# Board_OLED.net
KiCad netlist of a schematic drawn in EAGLE
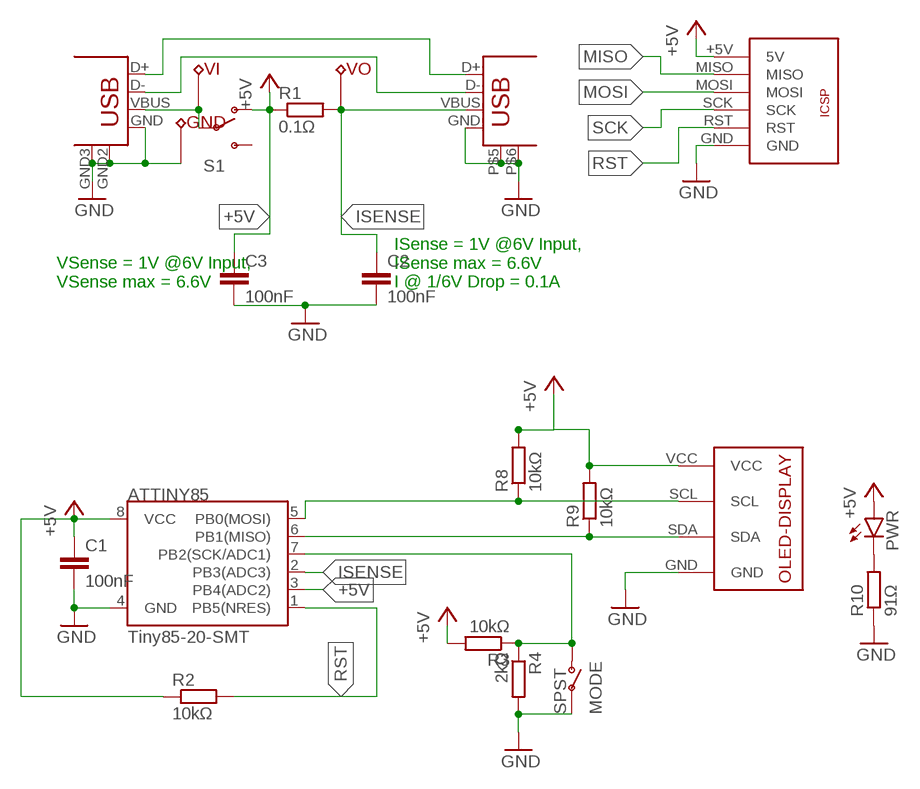
[diagram p0: schematic, sheet 1]

(export (version "E")
  (design (tool "Eeschema 10.0.6"))
  (components
    (comp (ref "ATTINY85")
      (value "Tiny85-20-SMT")
      (footprint "eagle-import:SO08-EIAJ")
      (libsource (lib "eagle-import") (part "ATTINY45TINY85-20-SMT"))
    )
    (comp (ref "C1")
      (value "100nF")
      (footprint "eagle-import:C0603")
      (libsource (lib "eagle-import") (part "C-EUC0603"))
    )
    (comp (ref "C2")
      (value "100nF")
      (footprint "eagle-import:C0603")
      (libsource (lib "eagle-import") (part "C-EUC0603"))
    )
    (comp (ref "C3")
      (value "100nF")
      (footprint "eagle-import:C0603")
      (libsource (lib "eagle-import") (part "C-EUC0603"))
    )
    (comp (ref "GND")
      (value "TESTPOINT0.5MM-DRILL-WIRE-LOOP")
      (footprint "eagle-import:TP-0.5MM-DUAL")
      (libsource (lib "eagle-import") (part "TESTPOINT0.5MM-DRILL-WIRE-LOOP"))
    )
    (comp (ref "INPUT")
      (value "USB+SHIELDTHROUGHHOLE-MALE")
      (footprint "eagle-import:USB-A-H")
      (libsource (lib "eagle-import") (part "USB+SHIELDTHROUGHHOLE-MALE"))
    )
    (comp (ref "MODE")
      (value "SPST")
      (footprint "eagle-import:WUERTH-SPST-SMD")
      (libsource (lib "eagle-import") (part "SPST"))
    )
    (comp (ref "OUTPUT")
      (value "USB+SHIELDTHROUGHOLE-FEMALE")
      (footprint "eagle-import:USB-A-S-SILK-THROUGHHOLE")
      (libsource (lib "eagle-import") (part "USB+SHIELDTHROUGHOLE-FEMALE"))
    )
    (comp (ref "PWR")
      (value "LED0603")
      (footprint "eagle-import:LED-0603")
      (libsource (lib "eagle-import") (part "LED0603"))
    )
    (comp (ref "R1")
      (value "0.1Ω")
      (footprint "eagle-import:R2512")
      (libsource (lib "eagle-import") (part "R-EU_R2512"))
    )
    (comp (ref "R2")
      (value "10kΩ")
      (footprint "eagle-import:R0603")
      (libsource (lib "eagle-import") (part "R-EU_R0603"))
    )
    (comp (ref "R3")
      (value "10kΩ")
      (footprint "eagle-import:R0603")
      (libsource (lib "eagle-import") (part "R-EU_R0603"))
    )
    (comp (ref "R4")
      (value "2kΩ")
      (footprint "eagle-import:R0603")
      (libsource (lib "eagle-import") (part "R-EU_R0603"))
    )
    (comp (ref "R8")
      (value "10kΩ")
      (footprint "eagle-import:R0603")
      (libsource (lib "eagle-import") (part "R-EU_R0603"))
    )
    (comp (ref "R9")
      (value "10kΩ")
      (footprint "eagle-import:R0603")
      (libsource (lib "eagle-import") (part "R-EU_R0603"))
    )
    (comp (ref "R10")
      (value "91Ω")
      (footprint "eagle-import:R0603")
      (libsource (lib "eagle-import") (part "R-EU_R0603"))
    )
    (comp (ref "S1")
      (value "SWITCH-SPDT-SMD-A")
      (footprint "eagle-import:SWITCH-SPST-SMD-A")
      (libsource (lib "eagle-import") (part "SWITCH-SPDT-SMD-A"))
    )
    (comp (ref "U$1")
      (value "ICSPSMD")
      (footprint "eagle-import:ICSP-SMD")
      (libsource (lib "eagle-import") (part "ICSPSMD"))
    )
    (comp (ref "U$2")
      (value "OLED-I2CGND-VCC-SCL-SDA")
      (footprint "eagle-import:OLED-I2C")
      (libsource (lib "eagle-import") (part "OLED-I2CGND-VCC-SCL-SDA"))
    )
    (comp (ref "VI")
      (value "TESTPOINT0.5MM-DRILL-WIRE-LOOP")
      (footprint "eagle-import:TP-0.5MM-DUAL")
      (libsource (lib "eagle-import") (part "TESTPOINT0.5MM-DRILL-WIRE-LOOP"))
    )
    (comp (ref "VO")
      (value "TESTPOINT0.5MM-DRILL-WIRE-LOOP")
      (footprint "eagle-import:TP-0.5MM-DUAL")
      (libsource (lib "eagle-import") (part "TESTPOINT0.5MM-DRILL-WIRE-LOOP"))
    )
  )
  (nets
    (net (code "1") (name "+5V") (class "Default")
      (node (ref "ATTINY85") (pin "3") (pinfunction "PB4(ADC2)_3") (pintype "bidirectional"))
      (node (ref "ATTINY85") (pin "8") (pinfunction "VCC_8") (pintype "bidirectional"))
      (node (ref "C1") (pin "1") (pinfunction "1_1") (pintype "passive"))
      (node (ref "C3") (pin "1") (pinfunction "1_1") (pintype "passive"))
      (node (ref "PWR") (pin "A") (pinfunction "A_A") (pintype "passive"))
      (node (ref "R1") (pin "1") (pinfunction "1_1") (pintype "passive"))
      (node (ref "R2") (pin "1") (pinfunction "1_1") (pintype "passive"))
      (node (ref "R3") (pin "2") (pinfunction "2_2") (pintype "passive"))
      (node (ref "R8") (pin "2") (pinfunction "2_2") (pintype "passive"))
      (node (ref "R9") (pin "2") (pinfunction "2_2") (pintype "passive"))
      (node (ref "S1") (pin "1") (pinfunction "O_1") (pintype "passive"))
      (node (ref "U$1") (pin "+5V") (pinfunction "5V_+5V") (pintype "bidirectional"))
      (node (ref "U$2") (pin "VCC") (pinfunction "VCC_VCC") (pintype "bidirectional"))
    )
    (net (code "2") (name "GND") (class "Default")
      (node (ref "ATTINY85") (pin "4") (pinfunction "GND_4") (pintype "bidirectional"))
      (node (ref "C1") (pin "2") (pinfunction "2_2") (pintype "passive"))
      (node (ref "C2") (pin "2") (pinfunction "2_2") (pintype "passive"))
      (node (ref "C3") (pin "2") (pinfunction "2_2") (pintype "passive"))
      (node (ref "GND") (pin "P$1") (pinfunction "TP_P$1") (pintype "bidirectional"))
      (node (ref "GND") (pin "P$2") (pinfunction "TP_P$2") (pintype "bidirectional"))
      (node (ref "INPUT") (pin "GND") (pinfunction "GND_GND") (pintype "bidirectional"))
      (node (ref "INPUT") (pin "GND2") (pinfunction "S1_GND2") (pintype "bidirectional"))
      (node (ref "INPUT") (pin "GND3") (pinfunction "S2_GND3") (pintype "bidirectional"))
      (node (ref "MODE") (pin "1") (pinfunction "P_1") (pintype "passive"))
      (node (ref "MODE") (pin "3") (pinfunction "P_3") (pintype "passive"))
      (node (ref "OUTPUT") (pin "GND") (pinfunction "GND_GND") (pintype "bidirectional"))
      (node (ref "OUTPUT") (pin "P$5") (pinfunction "S1_P$5") (pintype "bidirectional"))
      (node (ref "OUTPUT") (pin "P$6") (pinfunction "S2_P$6") (pintype "bidirectional"))
      (node (ref "R10") (pin "1") (pinfunction "1_1") (pintype "passive"))
      (node (ref "R4") (pin "2") (pinfunction "2_2") (pintype "passive"))
      (node (ref "U$1") (pin "GND") (pinfunction "GND_GND") (pintype "bidirectional"))
      (node (ref "U$2") (pin "GND") (pinfunction "GND_GND") (pintype "bidirectional"))
    )
    (net (code "3") (name "ISENSE") (class "Default")
      (node (ref "ATTINY85") (pin "2") (pinfunction "PB3(ADC3)_2") (pintype "bidirectional"))
      (node (ref "C2") (pin "1") (pinfunction "1_1") (pintype "passive"))
      (node (ref "OUTPUT") (pin "VBUS") (pinfunction "VBUS_VBUS") (pintype "bidirectional"))
      (node (ref "R1") (pin "2") (pinfunction "2_2") (pintype "passive"))
      (node (ref "VO") (pin "P$1") (pinfunction "TP_P$1") (pintype "bidirectional"))
      (node (ref "VO") (pin "P$2") (pinfunction "TP_P$2") (pintype "bidirectional"))
    )
    (net (code "4") (name "MISO") (class "Default")
      (node (ref "ATTINY85") (pin "6") (pinfunction "PB1(MISO)_6") (pintype "bidirectional"))
      (node (ref "R9") (pin "1") (pinfunction "1_1") (pintype "passive"))
      (node (ref "U$1") (pin "MISO") (pinfunction "MISO_MISO") (pintype "bidirectional"))
      (node (ref "U$2") (pin "SDA") (pinfunction "SDA_SDA") (pintype "bidirectional"))
    )
    (net (code "5") (name "MOSI") (class "Default")
      (node (ref "ATTINY85") (pin "5") (pinfunction "PB0(MOSI)_5") (pintype "bidirectional"))
      (node (ref "R8") (pin "1") (pinfunction "1_1") (pintype "passive"))
      (node (ref "U$1") (pin "MOSI") (pinfunction "MOSI_MOSI") (pintype "bidirectional"))
      (node (ref "U$2") (pin "SCL") (pinfunction "SCL_SCL") (pintype "bidirectional"))
    )
    (net (code "6") (name "Net-(INPUT-PadD+)") (class "Default")
      (node (ref "INPUT") (pin "D+") (pinfunction "D+_D+") (pintype "bidirectional"))
      (node (ref "OUTPUT") (pin "D+") (pinfunction "D+_D+") (pintype "bidirectional"))
    )
    (net (code "7") (name "Net-(INPUT-PadD-)") (class "Default")
      (node (ref "INPUT") (pin "D-") (pinfunction "D-_D-") (pintype "bidirectional"))
      (node (ref "OUTPUT") (pin "D-") (pinfunction "D-_D-") (pintype "bidirectional"))
    )
    (net (code "8") (name "Net-(PWR-PadC)") (class "Default")
      (node (ref "PWR") (pin "C") (pinfunction "C_C") (pintype "passive"))
      (node (ref "R10") (pin "2") (pinfunction "2_2") (pintype "passive"))
    )
    (net (code "9") (name "Net-(S1-P)") (class "Default")
      (node (ref "INPUT") (pin "VBUS") (pinfunction "VBUS_VBUS") (pintype "bidirectional"))
      (node (ref "S1") (pin "2") (pinfunction "P_2") (pintype "passive"))
      (node (ref "VI") (pin "P$1") (pinfunction "TP_P$1") (pintype "bidirectional"))
      (node (ref "VI") (pin "P$2") (pinfunction "TP_P$2") (pintype "bidirectional"))
    )
    (net (code "10") (name "RST") (class "Default")
      (node (ref "ATTINY85") (pin "1") (pinfunction "PB5(NRES)_1") (pintype "bidirectional"))
      (node (ref "R2") (pin "2") (pinfunction "2_2") (pintype "passive"))
      (node (ref "U$1") (pin "RST") (pinfunction "RST_RST") (pintype "bidirectional"))
    )
    (net (code "11") (name "SCK") (class "Default")
      (node (ref "ATTINY85") (pin "7") (pinfunction "PB2(SCK/ADC1)_7") (pintype "bidirectional"))
      (node (ref "MODE") (pin "2") (pinfunction "O_2") (pintype "passive"))
      (node (ref "MODE") (pin "4") (pinfunction "O_4") (pintype "passive"))
      (node (ref "R3") (pin "1") (pinfunction "1_1") (pintype "passive"))
      (node (ref "R4") (pin "1") (pinfunction "1_1") (pintype "passive"))
      (node (ref "U$1") (pin "SCK") (pinfunction "SCK_SCK") (pintype "bidirectional"))
    )
    (net (code "12") (name "unconnected-(S1-S-Pad3)") (class "Default")
      (node (ref "S1") (pin "3") (pinfunction "S_3") (pintype "passive"))
    )
  )
)
